# Main.net
KiCad netlist of a schematic drawn in Altium Designer
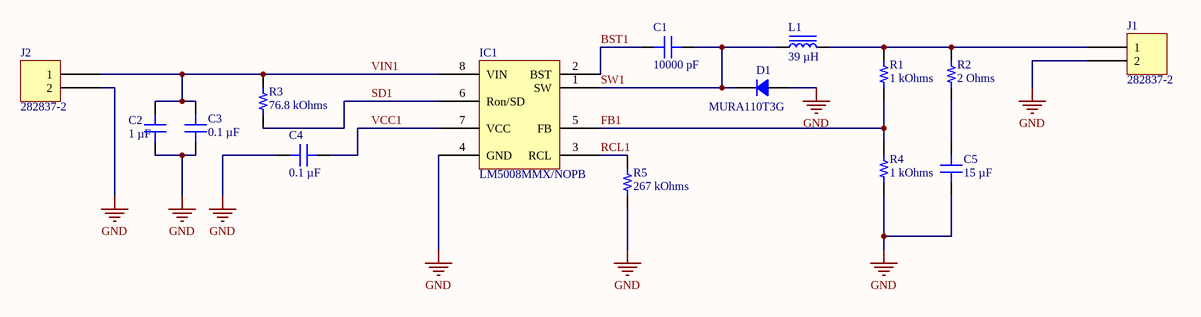
[diagram p0: Main.SchDoc]

(export (version "E")
  (design (tool "Eeschema 10.0.6"))
  (components
    (comp (ref "C1")
      (value "10000 pF")
      (footprint "CAP 0603_1608")
      (description "CAP CER 10000PF 100V X7R 0603")
      (fields (field (name "PART NUMBER") "AC0603KRX7R0BB103") (field (name "MANUFACTURER") "Yageo"))
      (libsource (lib "Celestial Altium Library - altium_library") (part "Capacitor"))
    )
    (comp (ref "C2")
      (value "1 µF")
      (footprint "CAP 0603_1608")
      (description "CAP CER 1UF 50V X5R 0603")
      (fields (field (name "PART NUMBER") "UMK107ABJ105MAHT") (field (name "MANUFACTURER") "Taiyo Yuden"))
      (libsource (lib "Celestial Altium Library - altium_library") (part "Capacitor"))
    )
    (comp (ref "C3")
      (value "0.1 µF")
      (footprint "CAP 0603_1608")
      (description "CAP CER 0.1UF 50V X7R 0603")
      (fields (field (name "PART NUMBER") "C0603C104K5RAC7411") (field (name "MANUFACTURER") "KEMET"))
      (libsource (lib "Celestial Altium Library - altium_library") (part "Capacitor"))
    )
    (comp (ref "C4")
      (value "0.1 µF")
      (footprint "CAP 0603_1608")
      (description "CAP CER 0.1UF 50V X7R 0603")
      (fields (field (name "PART NUMBER") "C0603C104K5RAC7411") (field (name "MANUFACTURER") "KEMET"))
      (libsource (lib "Celestial Altium Library - altium_library") (part "Capacitor"))
    )
    (comp (ref "C5")
      (value "15 µF")
      (footprint "CAP 0603_1608")
      (description "CAP CER 15UF 6.3V X5R 0603")
      (fields
        (field (name "PART NUMBER") "C1608X5R0J156M080AC")
        (field (name "MANUFACTURER") "TDK Corporation")
      )
      (libsource (lib "Celestial Altium Library - altium_library") (part "Capacitor"))
    )
    (comp (ref "D1")
      (value "MURA110T3G")
      (footprint "DO214AC SMA")
      (description "DIODE GEN PURP 100V 2A SMA")
      (fields (field (name "MANUFACTURER") "ON Semiconductor"))
      (libsource (lib "Celestial Altium Library - altium_library") (part "Diode"))
    )
    (comp (ref "IC1")
      (value "LM5008MMX/NOPB")
      (footprint "TI VSSOP-8 DGK")
      (description "IC REG BUCK ADJ 350MA 8VSSOP")
      (fields (field (name "MANUFACTURER") "Texas Instruments"))
      (libsource (lib "Celestial Altium Library - altium_library") (part "TI LM5008"))
    )
    (comp (ref "J1")
      (value "282837-2")
      (footprint "TE 282837-2")
      (description "TERM BLK 2P SIDE ENT 5.08MM PCB")
      (fields (field (name "MANUFACTURER") "TE Connectivity AMP Connectors") (field (name "VOLTAGE") "300 V"))
      (libsource (lib "") (part "282837-2_1"))
    )
    (comp (ref "J2")
      (value "282837-2")
      (footprint "TE 282837-2")
      (description "TERM BLK 2P SIDE ENT 5.08MM PCB")
      (fields (field (name "MANUFACTURER") "TE Connectivity AMP Connectors") (field (name "VOLTAGE") "300 V"))
      (libsource (lib "DC_Buck_Converter_5V") (part "282837-2"))
    )
    (comp (ref "L1")
      (value "39 µH")
      (footprint "BOURNS SRR1280")
      (description "FIXED IND 39UH 3.2A 70 MOHM SMD")
      (fields (field (name "PART NUMBER") "SRR1280-390M") (field (name "MANUFACTURER") "Bourns Inc."))
      (libsource (lib "Celestial Altium Library - altium_library") (part "Inductor"))
    )
    (comp (ref "R1")
      (value "1 kOhms")
      (footprint "RES 0603_1608")
      (description "RES SMD 1K OHM 0.5% 1/10W 0603")
      (fields (field (name "PART NUMBER") "AT0603DRD071KL") (field (name "MANUFACTURER") "Yageo"))
      (libsource (lib "Celestial Altium Library - altium_library") (part "Resistor"))
    )
    (comp (ref "R2")
      (value "2 Ohms")
      (footprint "RES 0603_1608")
      (description "SULFUR TOLERANT CHIP RESISTORS")
      (fields (field (name "PART NUMBER") "SFR03EZPJ2R0") (field (name "MANUFACTURER") "Rohm Semiconductor"))
      (libsource (lib "Celestial Altium Library - altium_library") (part "Resistor"))
    )
    (comp (ref "R3")
      (value "76.8 kOhms")
      (footprint "RES 0603_1608")
      (description "RES SMD 76.8KOHM 0.1% 1/10W 0603")
      (fields (field (name "PART NUMBER") "RG1608P-7682-B-T5") (field (name "MANUFACTURER") "Susumu"))
      (libsource (lib "Celestial Altium Library - altium_library") (part "Resistor"))
    )
    (comp (ref "R4")
      (value "1 kOhms")
      (footprint "RES 0603_1608")
      (description "RES SMD 1K OHM 0.5% 1/10W 0603")
      (fields (field (name "PART NUMBER") "AT0603DRD071KL") (field (name "MANUFACTURER") "Yageo"))
      (libsource (lib "Celestial Altium Library - altium_library") (part "Resistor"))
    )
    (comp (ref "R5")
      (value "267 kOhms")
      (footprint "RES 0603_1608")
      (description "RES SMD 267K OHM 0.1% 1/10W 0603")
      (fields (field (name "PART NUMBER") "RT0603BRD07267KL") (field (name "MANUFACTURER") "Yageo"))
      (libsource (lib "Celestial Altium Library - altium_library") (part "Resistor"))
    )
  )
  (nets
    (net (code "1") (name "/BST1") (class "Default")
      (node (ref "C1") (pin "1") (pinfunction "1_1") (pintype "passive"))
      (node (ref "IC1") (pin "2") (pinfunction "BST_2") (pintype "passive"))
    )
    (net (code "2") (name "/FB1") (class "Default")
      (node (ref "IC1") (pin "5") (pinfunction "FB_5") (pintype "passive"))
      (node (ref "R1") (pin "1") (pinfunction "1_1") (pintype "passive"))
      (node (ref "R4") (pin "2") (pinfunction "2_2") (pintype "passive"))
    )
    (net (code "3") (name "/RCL1") (class "Default")
      (node (ref "IC1") (pin "3") (pinfunction "RCL_3") (pintype "passive"))
      (node (ref "R5") (pin "2") (pinfunction "2_2") (pintype "passive"))
    )
    (net (code "4") (name "/SD1") (class "Default")
      (node (ref "IC1") (pin "6") (pinfunction "Ron/SD_6") (pintype "passive"))
      (node (ref "R3") (pin "1") (pinfunction "1_1") (pintype "passive"))
    )
    (net (code "5") (name "/SW1") (class "Default")
      (node (ref "C1") (pin "2") (pinfunction "2_2") (pintype "passive"))
      (node (ref "D1") (pin "2") (pinfunction "2_2") (pintype "passive"))
      (node (ref "IC1") (pin "1") (pinfunction "SW_1") (pintype "passive"))
      (node (ref "L1") (pin "1") (pinfunction "1_1") (pintype "passive"))
    )
    (net (code "6") (name "/VCC1") (class "Default")
      (node (ref "C4") (pin "1") (pinfunction "1_1") (pintype "passive"))
      (node (ref "IC1") (pin "7") (pinfunction "VCC_7") (pintype "passive"))
    )
    (net (code "7") (name "/VIN1") (class "Default")
      (node (ref "C2") (pin "2") (pinfunction "2_2") (pintype "passive"))
      (node (ref "C3") (pin "2") (pinfunction "2_2") (pintype "passive"))
      (node (ref "IC1") (pin "8") (pinfunction "VIN_8") (pintype "passive"))
      (node (ref "J2") (pin "1") (pinfunction "1_1") (pintype "passive"))
      (node (ref "R3") (pin "2") (pinfunction "2_2") (pintype "passive"))
    )
    (net (code "8") (name "GND") (class "Default")
      (node (ref "C2") (pin "1") (pinfunction "1_1") (pintype "passive"))
      (node (ref "C3") (pin "1") (pinfunction "1_1") (pintype "passive"))
      (node (ref "C4") (pin "2") (pinfunction "2_2") (pintype "passive"))
      (node (ref "C5") (pin "1") (pinfunction "1_1") (pintype "passive"))
      (node (ref "D1") (pin "1") (pinfunction "1_1") (pintype "passive"))
      (node (ref "IC1") (pin "4") (pinfunction "GND_4") (pintype "passive"))
      (node (ref "J1") (pin "2") (pinfunction "2_2") (pintype "passive"))
      (node (ref "J2") (pin "2") (pinfunction "2_2") (pintype "passive"))
      (node (ref "R4") (pin "1") (pinfunction "1_1") (pintype "passive"))
      (node (ref "R5") (pin "1") (pinfunction "1_1") (pintype "passive"))
    )
    (net (code "9") (name "Net-(C5-Pad2)") (class "Default")
      (node (ref "C5") (pin "2") (pinfunction "2_2") (pintype "passive"))
      (node (ref "R2") (pin "1") (pinfunction "1_1") (pintype "passive"))
    )
    (net (code "10") (name "Net-(J1-Pad1)") (class "Default")
      (node (ref "J1") (pin "1") (pinfunction "1_1") (pintype "passive"))
      (node (ref "L1") (pin "2") (pinfunction "2_2") (pintype "passive"))
      (node (ref "R1") (pin "2") (pinfunction "2_2") (pintype "passive"))
      (node (ref "R2") (pin "2") (pinfunction "2_2") (pintype "passive"))
    )
  )
)
